# laserdriver_v3_1.net
KiCad netlist of a schematic drawn in EAGLE
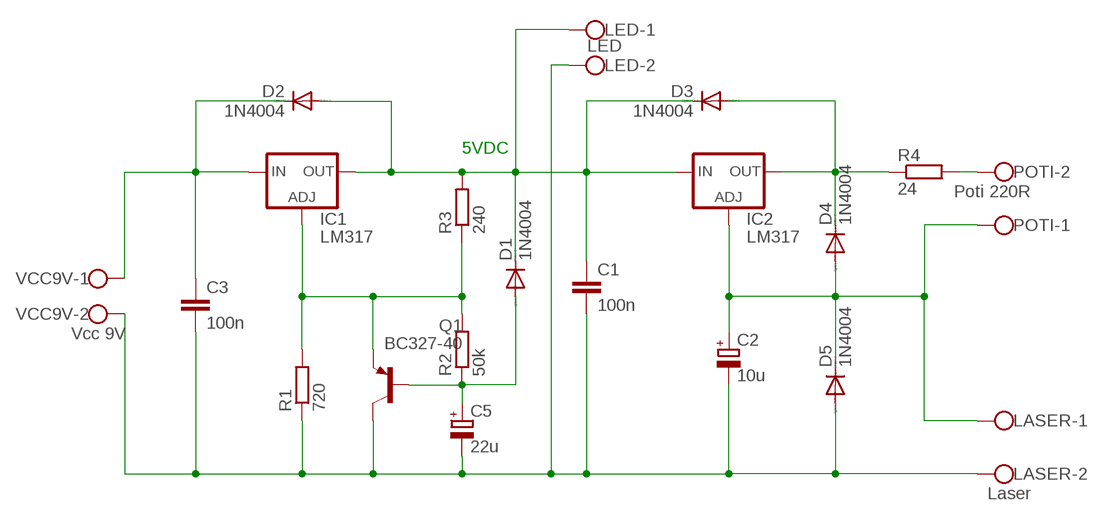
[diagram p0: schematic, sheet 1]

(export (version "E")
  (design (tool "Eeschema 10.0.6"))
  (components
    (comp (ref "C1")
      (value "100n")
      (footprint "eagle-import:C050-024X044")
      (libsource (lib "eagle-import") (part "C-EU050-024X044"))
    )
    (comp (ref "C2")
      (value "10u")
      (footprint "eagle-import:E2-5")
      (libsource (lib "eagle-import") (part "CPOL-EUE2-5"))
    )
    (comp (ref "C3")
      (value "100n")
      (footprint "eagle-import:C050-024X044")
      (libsource (lib "eagle-import") (part "C-EU050-024X044"))
    )
    (comp (ref "C5")
      (value "22u")
      (footprint "eagle-import:E2-5")
      (libsource (lib "eagle-import") (part "CPOL-EUE2-5"))
    )
    (comp (ref "D1")
      (value "1N4004")
      (footprint "eagle-import:DO41-10")
      (libsource (lib "eagle-import") (part "1N4004"))
    )
    (comp (ref "D2")
      (value "1N4004")
      (footprint "eagle-import:DO41-10")
      (libsource (lib "eagle-import") (part "1N4004"))
    )
    (comp (ref "D3")
      (value "1N4004")
      (footprint "eagle-import:DO41-10")
      (libsource (lib "eagle-import") (part "1N4004"))
    )
    (comp (ref "D4")
      (value "1N4004")
      (footprint "eagle-import:DO41-10")
      (libsource (lib "eagle-import") (part "1N4004"))
    )
    (comp (ref "D5")
      (value "1N4004")
      (footprint "eagle-import:DO41-10")
      (libsource (lib "eagle-import") (part "1N4004"))
    )
    (comp (ref "IC1")
      (value "LM317")
      (footprint "eagle-import:317TS")
      (libsource (lib "eagle-import") (part "LM317TS"))
    )
    (comp (ref "IC2")
      (value "LM317")
      (footprint "eagle-import:317TS")
      (libsource (lib "eagle-import") (part "LM317TS"))
    )
    (comp (ref "LASER")
      (value "Laser")
      (footprint "eagle-import:W237-102")
      (fields (field (name "MPN") "237-102"))
      (libsource (lib "eagle-import") (part "W237-102"))
    )
    (comp (ref "LED")
      (value "LED")
      (footprint "eagle-import:W237-102")
      (fields (field (name "MPN") "237-102"))
      (libsource (lib "eagle-import") (part "W237-102"))
    )
    (comp (ref "POTI")
      (value "Poti 220R")
      (footprint "eagle-import:W237-102")
      (fields (field (name "MPN") "237-102"))
      (libsource (lib "eagle-import") (part "W237-102"))
    )
    (comp (ref "Q1")
      (value "BC327-40")
      (footprint "eagle-import:TO92-EBC")
      (libsource (lib "eagle-import") (part "BC327-40"))
    )
    (comp (ref "R1")
      (value "720")
      (footprint "eagle-import:0207_7")
      (libsource (lib "eagle-import") (part "R-EU_0207/7"))
    )
    (comp (ref "R2")
      (value "50k")
      (footprint "eagle-import:0207_7")
      (libsource (lib "eagle-import") (part "R-EU_0207/7"))
    )
    (comp (ref "R3")
      (value "240")
      (footprint "eagle-import:0207_7")
      (libsource (lib "eagle-import") (part "R-EU_0207/7"))
    )
    (comp (ref "R4")
      (value "24")
      (footprint "eagle-import:0207_7")
      (libsource (lib "eagle-import") (part "R-EU_0207/7"))
    )
    (comp (ref "VCC9V")
      (value "Vcc 9V")
      (footprint "eagle-import:W237-102")
      (fields (field (name "MPN") "237-102"))
      (libsource (lib "eagle-import") (part "W237-102"))
    )
  )
  (nets
    (net (code "1") (name "Net-(C5-Pad+)") (class "Default")
      (node (ref "C5") (pin "+") (pinfunction "+_+") (pintype "passive"))
      (node (ref "D1") (pin "A") (pinfunction "A_A") (pintype "passive"))
      (node (ref "Q1") (pin "B") (pinfunction "B_B") (pintype "passive"))
      (node (ref "R2") (pin "1") (pinfunction "1_1") (pintype "passive"))
    )
    (net (code "2") (name "Net-(IC1-ADJ)") (class "Default")
      (node (ref "IC1") (pin "1") (pinfunction "ADJ_1") (pintype "input"))
      (node (ref "Q1") (pin "E") (pinfunction "E_E") (pintype "passive"))
      (node (ref "R1") (pin "2") (pinfunction "2_2") (pintype "passive"))
      (node (ref "R2") (pin "2") (pinfunction "2_2") (pintype "passive"))
      (node (ref "R3") (pin "1") (pinfunction "1_1") (pintype "passive"))
    )
    (net (code "3") (name "Net-(IC1-IN)") (class "Default")
      (node (ref "C3") (pin "1") (pinfunction "1_1") (pintype "passive"))
      (node (ref "D2") (pin "C") (pinfunction "C_C") (pintype "passive"))
      (node (ref "IC1") (pin "3") (pinfunction "IN_3") (pintype "input"))
      (node (ref "VCC9V") (pin "1") (pinfunction "KL_1") (pintype "passive"))
    )
    (net (code "4") (name "Net-(IC1-OUT)") (class "Default")
      (node (ref "C1") (pin "1") (pinfunction "1_1") (pintype "passive"))
      (node (ref "D1") (pin "C") (pinfunction "C_C") (pintype "passive"))
      (node (ref "D2") (pin "A") (pinfunction "A_A") (pintype "passive"))
      (node (ref "D3") (pin "C") (pinfunction "C_C") (pintype "passive"))
      (node (ref "IC1") (pin "2") (pinfunction "OUT_2") (pintype "passive"))
      (node (ref "IC2") (pin "3") (pinfunction "IN_3") (pintype "input"))
      (node (ref "LED") (pin "1") (pinfunction "KL_1") (pintype "passive"))
      (node (ref "R3") (pin "2") (pinfunction "2_2") (pintype "passive"))
    )
    (net (code "5") (name "Net-(IC2-ADJ)") (class "Default")
      (node (ref "C2") (pin "+") (pinfunction "+_+") (pintype "passive"))
      (node (ref "D4") (pin "A") (pinfunction "A_A") (pintype "passive"))
      (node (ref "D5") (pin "C") (pinfunction "C_C") (pintype "passive"))
      (node (ref "IC2") (pin "1") (pinfunction "ADJ_1") (pintype "input"))
      (node (ref "LASER") (pin "1") (pinfunction "KL_1") (pintype "passive"))
      (node (ref "POTI") (pin "1") (pinfunction "KL_1") (pintype "passive"))
    )
    (net (code "6") (name "Net-(IC2-OUT)") (class "Default")
      (node (ref "D3") (pin "A") (pinfunction "A_A") (pintype "passive"))
      (node (ref "D4") (pin "C") (pinfunction "C_C") (pintype "passive"))
      (node (ref "IC2") (pin "2") (pinfunction "OUT_2") (pintype "passive"))
      (node (ref "R4") (pin "1") (pinfunction "1_1") (pintype "passive"))
    )
    (net (code "7") (name "Net-(LASERB-KL)") (class "Default")
      (node (ref "C1") (pin "2") (pinfunction "2_2") (pintype "passive"))
      (node (ref "C2") (pin "-") (pinfunction "-_-") (pintype "passive"))
      (node (ref "C3") (pin "2") (pinfunction "2_2") (pintype "passive"))
      (node (ref "C5") (pin "-") (pinfunction "-_-") (pintype "passive"))
      (node (ref "D5") (pin "A") (pinfunction "A_A") (pintype "passive"))
      (node (ref "LASER") (pin "2") (pinfunction "KL_2") (pintype "passive"))
      (node (ref "LED") (pin "2") (pinfunction "KL_2") (pintype "passive"))
      (node (ref "Q1") (pin "C") (pinfunction "C_C") (pintype "passive"))
      (node (ref "R1") (pin "1") (pinfunction "1_1") (pintype "passive"))
      (node (ref "VCC9V") (pin "2") (pinfunction "KL_2") (pintype "passive"))
    )
    (net (code "8") (name "Net-(POTIB-KL)") (class "Default")
      (node (ref "POTI") (pin "2") (pinfunction "KL_2") (pintype "passive"))
      (node (ref "R4") (pin "2") (pinfunction "2_2") (pintype "passive"))
    )
  )
)
